# line_sensor.net
KiCad netlist of a schematic drawn in EasyEDA Pro
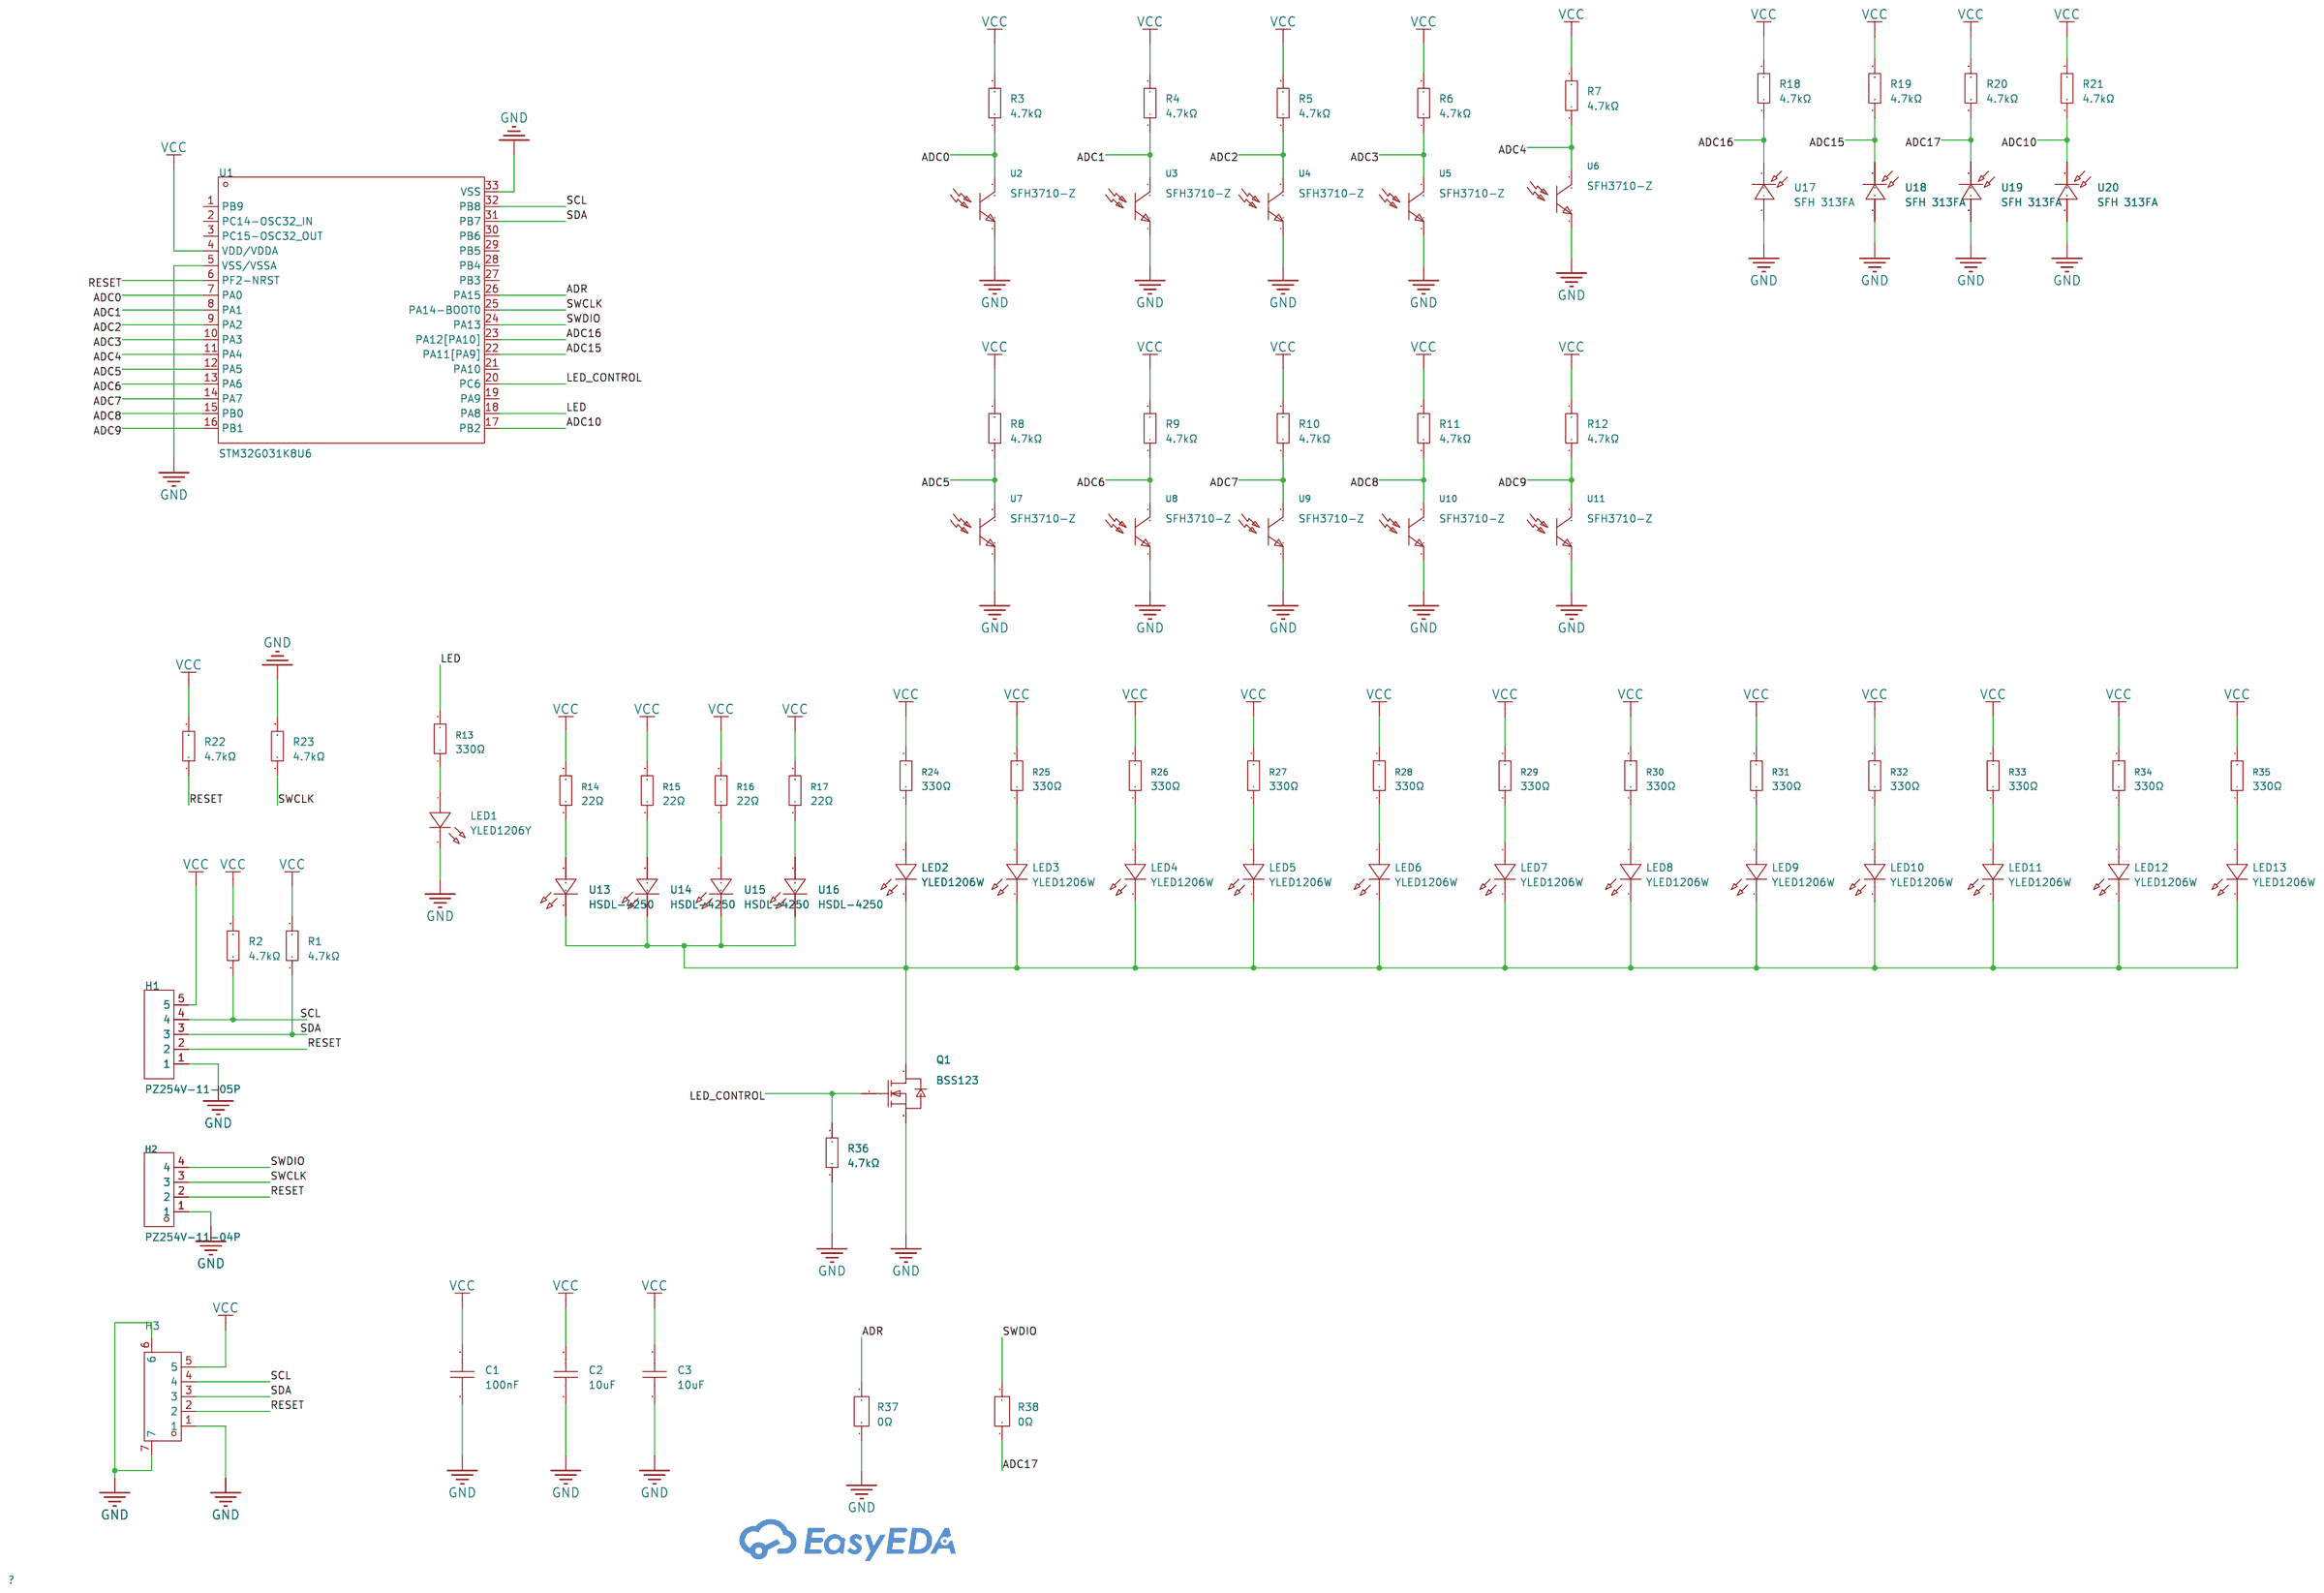
[diagram p0: schematic sheet]

(export (version "E")
  (design (tool "Eeschema 10.0.6"))
  (components
    (comp (ref "C1")
      (value "100nF")
      (footprint "easyedapro:C0805")
      (description "Capacitance:100nF Tolerance:±10% Tolerance:±10% Voltage Rating:50V Temperature Coefficient:X7R")
      (fields
        (field (name "Manufacturer Part") "CC0805KRX7R9BB104")
        (field (name "Manufacturer") "YAGEO(国巨)")
      )
      (libsource (lib "easyedapro") (part "CC0805KRX7R9BB104"))
    )
    (comp (ref "C2")
      (value "10uF")
      (footprint "easyedapro:C0805")
      (description "Capacitance:10uF Tolerance:±10% Tolerance:±10% Voltage Rating:50V Temperature Coefficient:X5R")
      (fields
        (field (name "Manufacturer Part") "CL21A106KBYQNNE")
        (field (name "Manufacturer") "SAMSUNG(三星)")
      )
      (libsource (lib "easyedapro") (part "CL21A106KBYQNNE"))
    )
    (comp (ref "C3")
      (value "10uF")
      (footprint "easyedapro:C0805")
      (description "Capacitance:10uF Tolerance:±10% Tolerance:±10% Voltage Rating:50V Temperature Coefficient:X5R")
      (fields
        (field (name "Manufacturer Part") "CL21A106KBYQNNE")
        (field (name "Manufacturer") "SAMSUNG(三星)")
      )
      (libsource (lib "easyedapro") (part "CL21A106KBYQNNE"))
    )
    (comp (ref "H1")
      (value "PZ254V-11-05P")
      (footprint "easyedapro:HDR-TH_5P-P2.54-V-M")
      (fields (field (name "Manufacturer") "XFCN(兴飞)"))
      (libsource (lib "easyedapro") (part "PZ254V-11-05P"))
    )
    (comp (ref "H2")
      (value "PZ254V-11-04P")
      (footprint "easyedapro:HDR-TH_4P-P2.54-V-M")
      (fields (field (name "Manufacturer") "XFCN(兴飞)"))
      (libsource (lib "easyedapro") (part "PZ254V-11-04P_C2691448"))
    )
    (comp (ref "H3")
      (value "GT-F0509SR15-05SMT01")
      (footprint "easyedapro:CONN-SMD_GT-F0509SR15-05SMT01")
      (fields (field (name "Manufacturer") "G-Switch(品赞)"))
      (libsource (lib "easyedapro") (part "GT-F0509SR15-05SMT01"))
    )
    (comp (ref "LED1")
      (value "YLED1206Y")
      (footprint "easyedapro:LED1206-FD")
      (fields (field (name "Manufacturer") "YONGYUTAI(永裕泰)"))
      (libsource (lib "easyedapro") (part "YLED1206Y"))
    )
    (comp (ref "LED2")
      (value "YLED1206W")
      (footprint "easyedapro:LED1206-R-RD")
      (fields (field (name "Manufacturer") "YONGYUTAI(永裕泰)"))
      (libsource (lib "easyedapro") (part "YLED1206W"))
    )
    (comp (ref "LED3")
      (value "YLED1206W")
      (footprint "easyedapro:LED1206-R-RD")
      (fields (field (name "Manufacturer") "YONGYUTAI(永裕泰)"))
      (libsource (lib "easyedapro") (part "YLED1206W"))
    )
    (comp (ref "LED4")
      (value "YLED1206W")
      (footprint "easyedapro:LED1206-R-RD")
      (fields (field (name "Manufacturer") "YONGYUTAI(永裕泰)"))
      (libsource (lib "easyedapro") (part "YLED1206W"))
    )
    (comp (ref "LED5")
      (value "YLED1206W")
      (footprint "easyedapro:LED1206-R-RD")
      (fields (field (name "Manufacturer") "YONGYUTAI(永裕泰)"))
      (libsource (lib "easyedapro") (part "YLED1206W"))
    )
    (comp (ref "LED6")
      (value "YLED1206W")
      (footprint "easyedapro:LED1206-R-RD")
      (fields (field (name "Manufacturer") "YONGYUTAI(永裕泰)"))
      (libsource (lib "easyedapro") (part "YLED1206W"))
    )
    (comp (ref "LED7")
      (value "YLED1206W")
      (footprint "easyedapro:LED1206-R-RD")
      (fields (field (name "Manufacturer") "YONGYUTAI(永裕泰)"))
      (libsource (lib "easyedapro") (part "YLED1206W"))
    )
    (comp (ref "LED8")
      (value "YLED1206W")
      (footprint "easyedapro:LED1206-R-RD")
      (fields (field (name "Manufacturer") "YONGYUTAI(永裕泰)"))
      (libsource (lib "easyedapro") (part "YLED1206W"))
    )
    (comp (ref "LED9")
      (value "YLED1206W")
      (footprint "easyedapro:LED1206-R-RD")
      (fields (field (name "Manufacturer") "YONGYUTAI(永裕泰)"))
      (libsource (lib "easyedapro") (part "YLED1206W"))
    )
    (comp (ref "LED10")
      (value "YLED1206W")
      (footprint "easyedapro:LED1206-R-RD")
      (fields (field (name "Manufacturer") "YONGYUTAI(永裕泰)"))
      (libsource (lib "easyedapro") (part "YLED1206W"))
    )
    (comp (ref "LED11")
      (value "YLED1206W")
      (footprint "easyedapro:LED1206-R-RD")
      (fields (field (name "Manufacturer") "YONGYUTAI(永裕泰)"))
      (libsource (lib "easyedapro") (part "YLED1206W"))
    )
    (comp (ref "LED12")
      (value "YLED1206W")
      (footprint "easyedapro:LED1206-R-RD")
      (fields (field (name "Manufacturer") "YONGYUTAI(永裕泰)"))
      (libsource (lib "easyedapro") (part "YLED1206W"))
    )
    (comp (ref "LED13")
      (value "YLED1206W")
      (footprint "easyedapro:LED1206-R-RD")
      (fields (field (name "Manufacturer") "YONGYUTAI(永裕泰)"))
      (libsource (lib "easyedapro") (part "YLED1206W"))
    )
    (comp (ref "Q1")
      (value "BSS123")
      (footprint "easyedapro:SOT-23-3_L3.0-W1.7-P0.95-LS2.9-BR")
      (fields (field (name "Manufacturer") "Siliup(矽普)"))
      (libsource (lib "easyedapro") (part "BSS123_C41355122"))
    )
    (comp (ref "R1")
      (value "4.7kΩ")
      (footprint "easyedapro:R0805")
      (fields
        (field (name "Manufacturer Part") "0805W8F4701T5E")
        (field (name "Manufacturer") "UNI-ROYAL(厚声)")
      )
      (libsource (lib "easyedapro") (part "0805W8F4701T5E"))
    )
    (comp (ref "R2")
      (value "4.7kΩ")
      (footprint "easyedapro:R0805")
      (fields
        (field (name "Manufacturer Part") "0805W8F4701T5E")
        (field (name "Manufacturer") "UNI-ROYAL(厚声)")
      )
      (libsource (lib "easyedapro") (part "0805W8F4701T5E"))
    )
    (comp (ref "R3")
      (value "4.7kΩ")
      (footprint "easyedapro:R0805")
      (fields
        (field (name "Manufacturer Part") "0805W8F4701T5E")
        (field (name "Manufacturer") "UNI-ROYAL(厚声)")
      )
      (libsource (lib "easyedapro") (part "0805W8F4701T5E"))
    )
    (comp (ref "R4")
      (value "4.7kΩ")
      (footprint "easyedapro:R0805")
      (fields
        (field (name "Manufacturer Part") "0805W8F4701T5E")
        (field (name "Manufacturer") "UNI-ROYAL(厚声)")
      )
      (libsource (lib "easyedapro") (part "0805W8F4701T5E"))
    )
    (comp (ref "R5")
      (value "4.7kΩ")
      (footprint "easyedapro:R0805")
      (fields
        (field (name "Manufacturer Part") "0805W8F4701T5E")
        (field (name "Manufacturer") "UNI-ROYAL(厚声)")
      )
      (libsource (lib "easyedapro") (part "0805W8F4701T5E"))
    )
    (comp (ref "R6")
      (value "4.7kΩ")
      (footprint "easyedapro:R0805")
      (fields
        (field (name "Manufacturer Part") "0805W8F4701T5E")
        (field (name "Manufacturer") "UNI-ROYAL(厚声)")
      )
      (libsource (lib "easyedapro") (part "0805W8F4701T5E"))
    )
    (comp (ref "R7")
      (value "4.7kΩ")
      (footprint "easyedapro:R0805")
      (fields
        (field (name "Manufacturer Part") "0805W8F4701T5E")
        (field (name "Manufacturer") "UNI-ROYAL(厚声)")
      )
      (libsource (lib "easyedapro") (part "0805W8F4701T5E"))
    )
    (comp (ref "R8")
      (value "4.7kΩ")
      (footprint "easyedapro:R0805")
      (fields
        (field (name "Manufacturer Part") "0805W8F4701T5E")
        (field (name "Manufacturer") "UNI-ROYAL(厚声)")
      )
      (libsource (lib "easyedapro") (part "0805W8F4701T5E"))
    )
    (comp (ref "R9")
      (value "4.7kΩ")
      (footprint "easyedapro:R0805")
      (fields
        (field (name "Manufacturer Part") "0805W8F4701T5E")
        (field (name "Manufacturer") "UNI-ROYAL(厚声)")
      )
      (libsource (lib "easyedapro") (part "0805W8F4701T5E"))
    )
    (comp (ref "R10")
      (value "4.7kΩ")
      (footprint "easyedapro:R0805")
      (fields
        (field (name "Manufacturer Part") "0805W8F4701T5E")
        (field (name "Manufacturer") "UNI-ROYAL(厚声)")
      )
      (libsource (lib "easyedapro") (part "0805W8F4701T5E"))
    )
    (comp (ref "R11")
      (value "4.7kΩ")
      (footprint "easyedapro:R0805")
      (fields
        (field (name "Manufacturer Part") "0805W8F4701T5E")
        (field (name "Manufacturer") "UNI-ROYAL(厚声)")
      )
      (libsource (lib "easyedapro") (part "0805W8F4701T5E"))
    )
    (comp (ref "R12")
      (value "4.7kΩ")
      (footprint "easyedapro:R0805")
      (fields
        (field (name "Manufacturer Part") "0805W8F4701T5E")
        (field (name "Manufacturer") "UNI-ROYAL(厚声)")
      )
      (libsource (lib "easyedapro") (part "0805W8F4701T5E"))
    )
    (comp (ref "R13")
      (value "330Ω")
      (footprint "easyedapro:R0805")
      (fields
        (field (name "Manufacturer Part") "0805W8F3300T5E")
        (field (name "Manufacturer") "UNI-ROYAL(厚声)")
      )
      (libsource (lib "easyedapro") (part "0805W8F3300T5E"))
    )
    (comp (ref "R14")
      (value "22Ω")
      (footprint "easyedapro:R0805")
      (fields
        (field (name "Manufacturer Part") "0805W8F3300T5E")
        (field (name "Manufacturer") "UNI-ROYAL(厚声)")
      )
      (libsource (lib "easyedapro") (part "0805W8F3300T5E"))
    )
    (comp (ref "R15")
      (value "22Ω")
      (footprint "easyedapro:R0805")
      (fields
        (field (name "Manufacturer Part") "0805W8F3300T5E")
        (field (name "Manufacturer") "UNI-ROYAL(厚声)")
      )
      (libsource (lib "easyedapro") (part "0805W8F3300T5E"))
    )
    (comp (ref "R16")
      (value "22Ω")
      (footprint "easyedapro:R0805")
      (fields
        (field (name "Manufacturer Part") "0805W8F3300T5E")
        (field (name "Manufacturer") "UNI-ROYAL(厚声)")
      )
      (libsource (lib "easyedapro") (part "0805W8F3300T5E"))
    )
    (comp (ref "R17")
      (value "22Ω")
      (footprint "easyedapro:R0805")
      (fields
        (field (name "Manufacturer Part") "0805W8F3300T5E")
        (field (name "Manufacturer") "UNI-ROYAL(厚声)")
      )
      (libsource (lib "easyedapro") (part "0805W8F3300T5E"))
    )
    (comp (ref "R18")
      (value "4.7kΩ")
      (footprint "easyedapro:R0805")
      (fields
        (field (name "Manufacturer Part") "0805W8F4701T5E")
        (field (name "Manufacturer") "UNI-ROYAL(厚声)")
      )
      (libsource (lib "easyedapro") (part "0805W8F4701T5E"))
    )
    (comp (ref "R19")
      (value "4.7kΩ")
      (footprint "easyedapro:R0805")
      (fields
        (field (name "Manufacturer Part") "0805W8F4701T5E")
        (field (name "Manufacturer") "UNI-ROYAL(厚声)")
      )
      (libsource (lib "easyedapro") (part "0805W8F4701T5E"))
    )
    (comp (ref "R20")
      (value "4.7kΩ")
      (footprint "easyedapro:R0805")
      (fields
        (field (name "Manufacturer Part") "0805W8F4701T5E")
        (field (name "Manufacturer") "UNI-ROYAL(厚声)")
      )
      (libsource (lib "easyedapro") (part "0805W8F4701T5E"))
    )
    (comp (ref "R21")
      (value "4.7kΩ")
      (footprint "easyedapro:R0805")
      (fields
        (field (name "Manufacturer Part") "0805W8F4701T5E")
        (field (name "Manufacturer") "UNI-ROYAL(厚声)")
      )
      (libsource (lib "easyedapro") (part "0805W8F4701T5E"))
    )
    (comp (ref "R22")
      (value "4.7kΩ")
      (footprint "easyedapro:R0805")
      (fields
        (field (name "Manufacturer Part") "0805W8F4701T5E")
        (field (name "Manufacturer") "UNI-ROYAL(厚声)")
      )
      (libsource (lib "easyedapro") (part "0805W8F4701T5E"))
    )
    (comp (ref "R23")
      (value "4.7kΩ")
      (footprint "easyedapro:R0805")
      (fields
        (field (name "Manufacturer Part") "0805W8F4701T5E")
        (field (name "Manufacturer") "UNI-ROYAL(厚声)")
      )
      (libsource (lib "easyedapro") (part "0805W8F4701T5E"))
    )
    (comp (ref "R24")
      (value "330Ω")
      (footprint "easyedapro:R0805")
      (fields
        (field (name "Manufacturer Part") "0805W8F3300T5E")
        (field (name "Manufacturer") "UNI-ROYAL(厚声)")
      )
      (libsource (lib "easyedapro") (part "0805W8F3300T5E"))
    )
    (comp (ref "R25")
      (value "330Ω")
      (footprint "easyedapro:R0805")
      (fields
        (field (name "Manufacturer Part") "0805W8F3300T5E")
        (field (name "Manufacturer") "UNI-ROYAL(厚声)")
      )
      (libsource (lib "easyedapro") (part "0805W8F3300T5E"))
    )
    (comp (ref "R26")
      (value "330Ω")
      (footprint "easyedapro:R0805")
      (fields
        (field (name "Manufacturer Part") "0805W8F3300T5E")
        (field (name "Manufacturer") "UNI-ROYAL(厚声)")
      )
      (libsource (lib "easyedapro") (part "0805W8F3300T5E"))
    )
    (comp (ref "R27")
      (value "330Ω")
      (footprint "easyedapro:R0805")
      (fields
        (field (name "Manufacturer Part") "0805W8F3300T5E")
        (field (name "Manufacturer") "UNI-ROYAL(厚声)")
      )
      (libsource (lib "easyedapro") (part "0805W8F3300T5E"))
    )
    (comp (ref "R28")
      (value "330Ω")
      (footprint "easyedapro:R0805")
      (fields
        (field (name "Manufacturer Part") "0805W8F3300T5E")
        (field (name "Manufacturer") "UNI-ROYAL(厚声)")
      )
      (libsource (lib "easyedapro") (part "0805W8F3300T5E"))
    )
    (comp (ref "R29")
      (value "330Ω")
      (footprint "easyedapro:R0805")
      (fields
        (field (name "Manufacturer Part") "0805W8F3300T5E")
        (field (name "Manufacturer") "UNI-ROYAL(厚声)")
      )
      (libsource (lib "easyedapro") (part "0805W8F3300T5E"))
    )
    (comp (ref "R30")
      (value "330Ω")
      (footprint "easyedapro:R0805")
      (fields
        (field (name "Manufacturer Part") "0805W8F3300T5E")
        (field (name "Manufacturer") "UNI-ROYAL(厚声)")
      )
      (libsource (lib "easyedapro") (part "0805W8F3300T5E"))
    )
    (comp (ref "R31")
      (value "330Ω")
      (footprint "easyedapro:R0805")
      (fields
        (field (name "Manufacturer Part") "0805W8F3300T5E")
        (field (name "Manufacturer") "UNI-ROYAL(厚声)")
      )
      (libsource (lib "easyedapro") (part "0805W8F3300T5E"))
    )
    (comp (ref "R32")
      (value "330Ω")
      (footprint "easyedapro:R0805")
      (fields
        (field (name "Manufacturer Part") "0805W8F3300T5E")
        (field (name "Manufacturer") "UNI-ROYAL(厚声)")
      )
      (libsource (lib "easyedapro") (part "0805W8F3300T5E"))
    )
    (comp (ref "R33")
      (value "330Ω")
      (footprint "easyedapro:R0805")
      (fields
        (field (name "Manufacturer Part") "0805W8F3300T5E")
        (field (name "Manufacturer") "UNI-ROYAL(厚声)")
      )
      (libsource (lib "easyedapro") (part "0805W8F3300T5E"))
    )
    (comp (ref "R34")
      (value "330Ω")
      (footprint "easyedapro:R0805")
      (fields
        (field (name "Manufacturer Part") "0805W8F3300T5E")
        (field (name "Manufacturer") "UNI-ROYAL(厚声)")
      )
      (libsource (lib "easyedapro") (part "0805W8F3300T5E"))
    )
    (comp (ref "R35")
      (value "330Ω")
      (footprint "easyedapro:R0805")
      (fields
        (field (name "Manufacturer Part") "0805W8F3300T5E")
        (field (name "Manufacturer") "UNI-ROYAL(厚声)")
      )
      (libsource (lib "easyedapro") (part "0805W8F3300T5E"))
    )
    (comp (ref "R36")
      (value "4.7kΩ")
      (footprint "easyedapro:R0805")
      (fields
        (field (name "Manufacturer Part") "0805W8F4701T5E")
        (field (name "Manufacturer") "UNI-ROYAL(厚声)")
      )
      (libsource (lib "easyedapro") (part "0805W8F4701T5E"))
    )
    (comp (ref "R37")
      (value "0Ω")
      (footprint "easyedapro:R0603")
      (fields (field (name "Manufacturer Part") "FRC0603P000 TS") (field (name "Manufacturer") "FOJAN(富捷)"))
      (libsource (lib "easyedapro") (part "FRC0603P000 TS"))
    )
    (comp (ref "R38")
      (value "0Ω")
      (footprint "easyedapro:R0603")
      (fields (field (name "Manufacturer Part") "FRC0603P000 TS") (field (name "Manufacturer") "FOJAN(富捷)"))
      (libsource (lib "easyedapro") (part "FRC0603P000 TS"))
    )
    (comp (ref "U1")
      (value "STM32G031K8U6")
      (footprint "easyedapro:UFQFPN-32_L5.0-W5.0-P0.50-BL-EP")
      (fields (field (name "Manufacturer") "ST(意法半导体)"))
      (libsource (lib "easyedapro") (part "STM32G031K8U6"))
    )
    (comp (ref "U2")
      (value "SFH3710-Z")
      (footprint "easyedapro:OPTO-SMD_SFH3710-Z")
      (fields (field (name "Manufacturer") "OSRAM(欧司朗)"))
      (libsource (lib "easyedapro") (part "SFH3710-Z"))
    )
    (comp (ref "U3")
      (value "SFH3710-Z")
      (footprint "easyedapro:OPTO-SMD_SFH3710-Z")
      (fields (field (name "Manufacturer") "OSRAM(欧司朗)"))
      (libsource (lib "easyedapro") (part "SFH3710-Z"))
    )
    (comp (ref "U4")
      (value "SFH3710-Z")
      (footprint "easyedapro:OPTO-SMD_SFH3710-Z")
      (fields (field (name "Manufacturer") "OSRAM(欧司朗)"))
      (libsource (lib "easyedapro") (part "SFH3710-Z"))
    )
    (comp (ref "U5")
      (value "SFH3710-Z")
      (footprint "easyedapro:OPTO-SMD_SFH3710-Z")
      (fields (field (name "Manufacturer") "OSRAM(欧司朗)"))
      (libsource (lib "easyedapro") (part "SFH3710-Z"))
    )
    (comp (ref "U6")
      (value "SFH3710-Z")
      (footprint "easyedapro:OPTO-SMD_SFH3710-Z")
      (fields (field (name "Manufacturer") "OSRAM(欧司朗)"))
      (libsource (lib "easyedapro") (part "SFH3710-Z"))
    )
    (comp (ref "U7")
      (value "SFH3710-Z")
      (footprint "easyedapro:OPTO-SMD_SFH3710-Z")
      (fields (field (name "Manufacturer") "OSRAM(欧司朗)"))
      (libsource (lib "easyedapro") (part "SFH3710-Z"))
    )
    (comp (ref "U8")
      (value "SFH3710-Z")
      (footprint "easyedapro:OPTO-SMD_SFH3710-Z")
      (fields (field (name "Manufacturer") "OSRAM(欧司朗)"))
      (libsource (lib "easyedapro") (part "SFH3710-Z"))
    )
    (comp (ref "U9")
      (value "SFH3710-Z")
      (footprint "easyedapro:OPTO-SMD_SFH3710-Z")
      (fields (field (name "Manufacturer") "OSRAM(欧司朗)"))
      (libsource (lib "easyedapro") (part "SFH3710-Z"))
    )
    (comp (ref "U10")
      (value "SFH3710-Z")
      (footprint "easyedapro:OPTO-SMD_SFH3710-Z")
      (fields (field (name "Manufacturer") "OSRAM(欧司朗)"))
      (libsource (lib "easyedapro") (part "SFH3710-Z"))
    )
    (comp (ref "U11")
      (value "SFH3710-Z")
      (footprint "easyedapro:OPTO-SMD_SFH3710-Z")
      (fields (field (name "Manufacturer") "OSRAM(欧司朗)"))
      (libsource (lib "easyedapro") (part "SFH3710-Z"))
    )
    (comp (ref "U13")
      (value "HSDL-4250")
      (footprint "easyedapro:LED-TH_BD5.0-P2.54-FD-1")
      (fields (field (name "Manufacturer") "LITEON(光宝)"))
      (libsource (lib "easyedapro") (part "HSDL-4250"))
    )
    (comp (ref "U14")
      (value "HSDL-4250")
      (footprint "easyedapro:LED-TH_BD5.0-P2.54-FD-1")
      (fields (field (name "Manufacturer") "LITEON(光宝)"))
      (libsource (lib "easyedapro") (part "HSDL-4250"))
    )
    (comp (ref "U15")
      (value "HSDL-4250")
      (footprint "easyedapro:LED-TH_BD5.0-P2.54-FD-1")
      (fields (field (name "Manufacturer") "LITEON(光宝)"))
      (libsource (lib "easyedapro") (part "HSDL-4250"))
    )
    (comp (ref "U16")
      (value "HSDL-4250")
      (footprint "easyedapro:LED-TH_BD5.0-P2.54-FD-1")
      (fields (field (name "Manufacturer") "LITEON(光宝)"))
      (libsource (lib "easyedapro") (part "HSDL-4250"))
    )
    (comp (ref "U17")
      (value "SFH 313FA")
      (footprint "easyedapro:OPTO-TH_BD5.7-P2.54-D0.8")
      (fields (field (name "Manufacturer") "OSRAM(欧司朗)"))
      (libsource (lib "easyedapro") (part "SFH 313FA"))
    )
    (comp (ref "U18")
      (value "SFH 313FA")
      (footprint "easyedapro:OPTO-TH_BD5.7-P2.54-D0.8")
      (fields (field (name "Manufacturer") "OSRAM(欧司朗)"))
      (libsource (lib "easyedapro") (part "SFH 313FA"))
    )
    (comp (ref "U19")
      (value "SFH 313FA")
      (footprint "easyedapro:OPTO-TH_BD5.7-P2.54-D0.8")
      (fields (field (name "Manufacturer") "OSRAM(欧司朗)"))
      (libsource (lib "easyedapro") (part "SFH 313FA"))
    )
    (comp (ref "U20")
      (value "SFH 313FA")
      (footprint "easyedapro:OPTO-TH_BD5.7-P2.54-D0.8")
      (fields (field (name "Manufacturer") "OSRAM(欧司朗)"))
      (libsource (lib "easyedapro") (part "SFH 313FA"))
    )
  )
  (nets
    (net (code "1") (name "/ADC0") (class "Default")
      (node (ref "R3") (pin "1") (pinfunction "1_1") (pintype "input"))
      (node (ref "U1") (pin "7") (pinfunction "PA0_7") (pintype "unspecified"))
      (node (ref "U2") (pin "2") (pinfunction "C_2") (pintype "input"))
    )
    (net (code "2") (name "/ADC1") (class "Default")
      (node (ref "R4") (pin "1") (pinfunction "1_1") (pintype "input"))
      (node (ref "U1") (pin "8") (pinfunction "PA1_8") (pintype "unspecified"))
      (node (ref "U3") (pin "2") (pinfunction "C_2") (pintype "input"))
    )
    (net (code "3") (name "/ADC2") (class "Default")
      (node (ref "R5") (pin "1") (pinfunction "1_1") (pintype "input"))
      (node (ref "U1") (pin "9") (pinfunction "PA2_9") (pintype "unspecified"))
      (node (ref "U4") (pin "2") (pinfunction "C_2") (pintype "input"))
    )
    (net (code "4") (name "/ADC3") (class "Default")
      (node (ref "R6") (pin "1") (pinfunction "1_1") (pintype "input"))
      (node (ref "U1") (pin "10") (pinfunction "PA3_10") (pintype "unspecified"))
      (node (ref "U5") (pin "2") (pinfunction "C_2") (pintype "input"))
    )
    (net (code "5") (name "/ADC4") (class "Default")
      (node (ref "R7") (pin "1") (pinfunction "1_1") (pintype "input"))
      (node (ref "U1") (pin "11") (pinfunction "PA4_11") (pintype "unspecified"))
      (node (ref "U6") (pin "2") (pinfunction "C_2") (pintype "input"))
    )
    (net (code "6") (name "/ADC5") (class "Default")
      (node (ref "R8") (pin "1") (pinfunction "1_1") (pintype "input"))
      (node (ref "U1") (pin "12") (pinfunction "PA5_12") (pintype "unspecified"))
      (node (ref "U7") (pin "2") (pinfunction "C_2") (pintype "input"))
    )
    (net (code "7") (name "/ADC6") (class "Default")
      (node (ref "R9") (pin "1") (pinfunction "1_1") (pintype "input"))
      (node (ref "U1") (pin "13") (pinfunction "PA6_13") (pintype "unspecified"))
      (node (ref "U8") (pin "2") (pinfunction "C_2") (pintype "input"))
    )
    (net (code "8") (name "/ADC7") (class "Default")
      (node (ref "R10") (pin "1") (pinfunction "1_1") (pintype "input"))
      (node (ref "U1") (pin "14") (pinfunction "PA7_14") (pintype "unspecified"))
      (node (ref "U9") (pin "2") (pinfunction "C_2") (pintype "input"))
    )
    (net (code "9") (name "/ADC8") (class "Default")
      (node (ref "R11") (pin "1") (pinfunction "1_1") (pintype "input"))
      (node (ref "U1") (pin "15") (pinfunction "PB0_15") (pintype "unspecified"))
      (node (ref "U10") (pin "2") (pinfunction "C_2") (pintype "input"))
    )
    (net (code "10") (name "/ADC9") (class "Default")
      (node (ref "R12") (pin "1") (pinfunction "1_1") (pintype "input"))
      (node (ref "U1") (pin "16") (pinfunction "PB1_16") (pintype "unspecified"))
      (node (ref "U11") (pin "2") (pinfunction "C_2") (pintype "input"))
    )
    (net (code "11") (name "/ADC10") (class "Default")
      (node (ref "R21") (pin "1") (pinfunction "1_1") (pintype "input"))
      (node (ref "U1") (pin "17") (pinfunction "PB2_17") (pintype "unspecified"))
      (node (ref "U20") (pin "1") (pinfunction "C_1") (pintype "unspecified"))
    )
    (net (code "12") (name "/ADC15") (class "Default")
      (node (ref "R19") (pin "1") (pinfunction "1_1") (pintype "input"))
      (node (ref "U1") (pin "22") (pinfunction "PA11[PA9]_22") (pintype "unspecified"))
      (node (ref "U18") (pin "1") (pinfunction "C_1") (pintype "unspecified"))
    )
    (net (code "13") (name "/ADC16") (class "Default")
      (node (ref "R18") (pin "1") (pinfunction "1_1") (pintype "input"))
      (node (ref "U1") (pin "23") (pinfunction "PA12[PA10]_23") (pintype "unspecified"))
      (node (ref "U17") (pin "1") (pinfunction "C_1") (pintype "unspecified"))
    )
    (net (code "14") (name "/ADC17") (class "Default")
      (node (ref "R20") (pin "1") (pinfunction "1_1") (pintype "input"))
      (node (ref "R38") (pin "1") (pinfunction "1_1") (pintype "unspecified"))
      (node (ref "U19") (pin "1") (pinfunction "C_1") (pintype "unspecified"))
    )
    (net (code "15") (name "/ADR") (class "Default")
      (node (ref "R37") (pin "2") (pinfunction "2_2") (pintype "unspecified"))
      (node (ref "U1") (pin "26") (pinfunction "PA15_26") (pintype "unspecified"))
    )
    (net (code "16") (name "/LED") (class "Default")
      (node (ref "R13") (pin "2") (pinfunction "2_2") (pintype "input"))
      (node (ref "U1") (pin "18") (pinfunction "PA8_18") (pintype "unspecified"))
    )
    (net (code "17") (name "/LED_CONTROL") (class "Default")
      (node (ref "Q1") (pin "1") (pinfunction "G_1") (pintype "unspecified"))
      (node (ref "R36") (pin "2") (pinfunction "2_2") (pintype "input"))
      (node (ref "U1") (pin "20") (pinfunction "PC6_20") (pintype "unspecified"))
    )
    (net (code "18") (name "/RESET") (class "Default")
      (node (ref "H1") (pin "2") (pinfunction "2_2") (pintype "unspecified"))
      (node (ref "H2") (pin "2") (pinfunction "2_2") (pintype "input"))
      (node (ref "H3") (pin "2") (pinfunction "2_2") (pintype "unspecified"))
      (node (ref "R22") (pin "1") (pinfunction "1_1") (pintype "input"))
      (node (ref "U1") (pin "6") (pinfunction "PF2-NRST_6") (pintype "unspecified"))
    )
    (net (code "19") (name "/SCL") (class "Default")
      (node (ref "H1") (pin "4") (pinfunction "4_4") (pintype "unspecified"))
      (node (ref "H3") (pin "4") (pinfunction "4_4") (pintype "unspecified"))
      (node (ref "R2") (pin "1") (pinfunction "1_1") (pintype "input"))
      (node (ref "U1") (pin "32") (pinfunction "PB8_32") (pintype "unspecified"))
    )
    (net (code "20") (name "/SDA") (class "Default")
      (node (ref "H1") (pin "3") (pinfunction "3_3") (pintype "unspecified"))
      (node (ref "H3") (pin "3") (pinfunction "3_3") (pintype "unspecified"))
      (node (ref "R1") (pin "1") (pinfunction "1_1") (pintype "input"))
      (node (ref "U1") (pin "31") (pinfunction "PB7_31") (pintype "unspecified"))
    )
    (net (code "21") (name "/SWCLK") (class "Default")
      (node (ref "H2") (pin "3") (pinfunction "3_3") (pintype "input"))
      (node (ref "R23") (pin "1") (pinfunction "1_1") (pintype "input"))
      (node (ref "U1") (pin "25") (pinfunction "PA14-BOOT0_25") (pintype "unspecified"))
    )
    (net (code "22") (name "/SWDIO") (class "Default")
      (node (ref "H2") (pin "4") (pinfunction "4_4") (pintype "input"))
      (node (ref "R38") (pin "2") (pinfunction "2_2") (pintype "unspecified"))
      (node (ref "U1") (pin "24") (pinfunction "PA13_24") (pintype "unspecified"))
    )
    (net (code "23") (name "GND") (class "Default")
      (node (ref "C1") (pin "1") (pinfunction "1_1") (pintype "unspecified"))
      (node (ref "C2") (pin "1") (pinfunction "1_1") (pintype "unspecified"))
      (node (ref "C3") (pin "1") (pinfunction "1_1") (pintype "unspecified"))
      (node (ref "H1") (pin "1") (pinfunction "1_1") (pintype "unspecified"))
      (node (ref "H2") (pin "1") (pinfunction "1_1") (pintype "input"))
      (node (ref "H3") (pin "1") (pinfunction "1_1") (pintype "unspecified"))
      (node (ref "H3") (pin "6") (pinfunction "6_6") (pintype "unspecified"))
      (node (ref "H3") (pin "7") (pinfunction "7_7") (pintype "unspecified"))
      (node (ref "LED1") (pin "2") (pinfunction "C_2") (pintype "unspecified"))
      (node (ref "Q1") (pin "2") (pinfunction "S_2") (pintype "unspecified"))
      (node (ref "R23") (pin "2") (pinfunction "2_2") (pintype "input"))
      (node (ref "R36") (pin "1") (pinfunction "1_1") (pintype "input"))
      (node (ref "R37") (pin "1") (pinfunction "1_1") (pintype "unspecified"))
      (node (ref "U1") (pin "33") (pinfunction "VSS_33") (pintype "unspecified"))
      (node (ref "U1") (pin "5") (pinfunction "VSS/VSSA_5") (pintype "unspecified"))
      (node (ref "U10") (pin "1") (pinfunction "E_1") (pintype "input"))
      (node (ref "U11") (pin "1") (pinfunction "E_1") (pintype "input"))
      (node (ref "U17") (pin "2") (pinfunction "A_2") (pintype "unspecified"))
      (node (ref "U18") (pin "2") (pinfunction "A_2") (pintype "unspecified"))
      (node (ref "U19") (pin "2") (pinfunction "A_2") (pintype "unspecified"))
      (node (ref "U2") (pin "1") (pinfunction "E_1") (pintype "input"))
      (node (ref "U20") (pin "2") (pinfunction "A_2") (pintype "unspecified"))
      (node (ref "U3") (pin "1") (pinfunction "E_1") (pintype "input"))
      (node (ref "U4") (pin "1") (pinfunction "E_1") (pintype "input"))
      (node (ref "U5") (pin "1") (pinfunction "E_1") (pintype "input"))
      (node (ref "U6") (pin "1") (pinfunction "E_1") (pintype "input"))
      (node (ref "U7") (pin "1") (pinfunction "E_1") (pintype "input"))
      (node (ref "U8") (pin "1") (pinfunction "E_1") (pintype "input"))
      (node (ref "U9") (pin "1") (pinfunction "E_1") (pintype "input"))
    )
    (net (code "24") (name "Net-(LED1-A)") (class "Default")
      (node (ref "LED1") (pin "1") (pinfunction "A_1") (pintype "unspecified"))
      (node (ref "R13") (pin "1") (pinfunction "1_1") (pintype "input"))
    )
    (net (code "25") (name "Net-(LED2-A)") (class "Default")
      (node (ref "LED2") (pin "1") (pinfunction "A_1") (pintype "unspecified"))
      (node (ref "R24") (pin "1") (pinfunction "1_1") (pintype "input"))
    )
    (net (code "26") (name "Net-(LED3-A)") (class "Default")
      (node (ref "LED3") (pin "1") (pinfunction "A_1") (pintype "unspecified"))
      (node (ref "R25") (pin "1") (pinfunction "1_1") (pintype "input"))
    )
    (net (code "27") (name "Net-(LED4-A)") (class "Default")
      (node (ref "LED4") (pin "1") (pinfunction "A_1") (pintype "unspecified"))
      (node (ref "R26") (pin "1") (pinfunction "1_1") (pintype "input"))
    )
    (net (code "28") (name "Net-(LED5-A)") (class "Default")
      (node (ref "LED5") (pin "1") (pinfunction "A_1") (pintype "unspecified"))
      (node (ref "R27") (pin "1") (pinfunction "1_1") (pintype "input"))
    )
    (net (code "29") (name "Net-(LED6-A)") (class "Default")
      (node (ref "LED6") (pin "1") (pinfunction "A_1") (pintype "unspecified"))
      (node (ref "R28") (pin "1") (pinfunction "1_1") (pintype "input"))
    )
    (net (code "30") (name "Net-(LED7-A)") (class "Default")
      (node (ref "LED7") (pin "1") (pinfunction "A_1") (pintype "unspecified"))
      (node (ref "R29") (pin "1") (pinfunction "1_1") (pintype "input"))
    )
    (net (code "31") (name "Net-(LED8-A)") (class "Default")
      (node (ref "LED8") (pin "1") (pinfunction "A_1") (pintype "unspecified"))
      (node (ref "R30") (pin "1") (pinfunction "1_1") (pintype "input"))
    )
    (net (code "32") (name "Net-(LED9-A)") (class "Default")
      (node (ref "LED9") (pin "1") (pinfunction "A_1") (pintype "unspecified"))
      (node (ref "R31") (pin "1") (pinfunction "1_1") (pintype "input"))
    )
    (net (code "33") (name "Net-(LED10-A)") (class "Default")
      (node (ref "LED10") (pin "1") (pinfunction "A_1") (pintype "unspecified"))
      (node (ref "R32") (pin "1") (pinfunction "1_1") (pintype "input"))
    )
    (net (code "34") (name "Net-(LED10-K)") (class "Default")
      (node (ref "LED10") (pin "2") (pinfunction "K_2") (pintype "unspecified"))
      (node (ref "LED11") (pin "2") (pinfunction "K_2") (pintype "unspecified"))
      (node (ref "LED12") (pin "2") (pinfunction "K_2") (pintype "unspecified"))
      (node (ref "LED13") (pin "2") (pinfunction "K_2") (pintype "unspecified"))
      (node (ref "LED2") (pin "2") (pinfunction "K_2") (pintype "unspecified"))
      (node (ref "LED3") (pin "2") (pinfunction "K_2") (pintype "unspecified"))
      (node (ref "LED4") (pin "2") (pinfunction "K_2") (pintype "unspecified"))
      (node (ref "LED5") (pin "2") (pinfunction "K_2") (pintype "unspecified"))
      (node (ref "LED6") (pin "2") (pinfunction "K_2") (pintype "unspecified"))
      (node (ref "LED7") (pin "2") (pinfunction "K_2") (pintype "unspecified"))
      (node (ref "LED8") (pin "2") (pinfunction "K_2") (pintype "unspecified"))
      (node (ref "LED9") (pin "2") (pinfunction "K_2") (pintype "unspecified"))
      (node (ref "Q1") (pin "3") (pinfunction "D_3") (pintype "unspecified"))
      (node (ref "U13") (pin "2") (pinfunction "C_2") (pintype "unspecified"))
      (node (ref "U14") (pin "2") (pinfunction "C_2") (pintype "unspecified"))
      (node (ref "U15") (pin "2") (pinfunction "C_2") (pintype "unspecified"))
      (node (ref "U16") (pin "2") (pinfunction "C_2") (pintype "unspecified"))
    )
    (net (code "35") (name "Net-(LED11-A)") (class "Default")
      (node (ref "LED11") (pin "1") (pinfunction "A_1") (pintype "unspecified"))
      (node (ref "R33") (pin "1") (pinfunction "1_1") (pintype "input"))
    )
    (net (code "36") (name "Net-(LED12-A)") (class "Default")
      (node (ref "LED12") (pin "1") (pinfunction "A_1") (pintype "unspecified"))
      (node (ref "R34") (pin "1") (pinfunction "1_1") (pintype "input"))
    )
    (net (code "37") (name "Net-(LED13-A)") (class "Default")
      (node (ref "LED13") (pin "1") (pinfunction "A_1") (pintype "unspecified"))
      (node (ref "R35") (pin "1") (pinfunction "1_1") (pintype "input"))
    )
    (net (code "38") (name "Net-(U13-A)") (class "Default")
      (node (ref "R14") (pin "1") (pinfunction "1_1") (pintype "input"))
      (node (ref "U13") (pin "1") (pinfunction "A_1") (pintype "unspecified"))
    )
    (net (code "39") (name "Net-(U14-A)") (class "Default")
      (node (ref "R15") (pin "1") (pinfunction "1_1") (pintype "input"))
      (node (ref "U14") (pin "1") (pinfunction "A_1") (pintype "unspecified"))
    )
    (net (code "40") (name "Net-(U15-A)") (class "Default")
      (node (ref "R16") (pin "1") (pinfunction "1_1") (pintype "input"))
      (node (ref "U15") (pin "1") (pinfunction "A_1") (pintype "unspecified"))
    )
    (net (code "41") (name "Net-(U16-A)") (class "Default")
      (node (ref "R17") (pin "1") (pinfunction "1_1") (pintype "input"))
      (node (ref "U16") (pin "1") (pinfunction "A_1") (pintype "unspecified"))
    )
    (net (code "42") (name "VCC") (class "Default")
      (node (ref "C1") (pin "2") (pinfunction "2_2") (pintype "unspecified"))
      (node (ref "C2") (pin "2") (pinfunction "2_2") (pintype "unspecified"))
      (node (ref "C3") (pin "2") (pinfunction "2_2") (pintype "unspecified"))
      (node (ref "H1") (pin "5") (pinfunction "5_5") (pintype "unspecified"))
      (node (ref "H3") (pin "5") (pinfunction "5_5") (pintype "unspecified"))
      (node (ref "R1") (pin "2") (pinfunction "2_2") (pintype "input"))
      (node (ref "R10") (pin "2") (pinfunction "2_2") (pintype "input"))
      (node (ref "R11") (pin "2") (pinfunction "2_2") (pintype "input"))
      (node (ref "R12") (pin "2") (pinfunction "2_2") (pintype "input"))
      (node (ref "R14") (pin "2") (pinfunction "2_2") (pintype "input"))
      (node (ref "R15") (pin "2") (pinfunction "2_2") (pintype "input"))
      (node (ref "R16") (pin "2") (pinfunction "2_2") (pintype "input"))
      (node (ref "R17") (pin "2") (pinfunction "2_2") (pintype "input"))
      (node (ref "R18") (pin "2") (pinfunction "2_2") (pintype "input"))
      (node (ref "R19") (pin "2") (pinfunction "2_2") (pintype "input"))
      (node (ref "R2") (pin "2") (pinfunction "2_2") (pintype "input"))
      (node (ref "R20") (pin "2") (pinfunction "2_2") (pintype "input"))
      (node (ref "R21") (pin "2") (pinfunction "2_2") (pintype "input"))
      (node (ref "R22") (pin "2") (pinfunction "2_2") (pintype "input"))
      (node (ref "R24") (pin "2") (pinfunction "2_2") (pintype "input"))
      (node (ref "R25") (pin "2") (pinfunction "2_2") (pintype "input"))
      (node (ref "R26") (pin "2") (pinfunction "2_2") (pintype "input"))
      (node (ref "R27") (pin "2") (pinfunction "2_2") (pintype "input"))
      (node (ref "R28") (pin "2") (pinfunction "2_2") (pintype "input"))
      (node (ref "R29") (pin "2") (pinfunction "2_2") (pintype "input"))
      (node (ref "R3") (pin "2") (pinfunction "2_2") (pintype "input"))
      (node (ref "R30") (pin "2") (pinfunction "2_2") (pintype "input"))
      (node (ref "R31") (pin "2") (pinfunction "2_2") (pintype "input"))
      (node (ref "R32") (pin "2") (pinfunction "2_2") (pintype "input"))
      (node (ref "R33") (pin "2") (pinfunction "2_2") (pintype "input"))
      (node (ref "R34") (pin "2") (pinfunction "2_2") (pintype "input"))
      (node (ref "R35") (pin "2") (pinfunction "2_2") (pintype "input"))
      (node (ref "R4") (pin "2") (pinfunction "2_2") (pintype "input"))
      (node (ref "R5") (pin "2") (pinfunction "2_2") (pintype "input"))
      (node (ref "R6") (pin "2") (pinfunction "2_2") (pintype "input"))
      (node (ref "R7") (pin "2") (pinfunction "2_2") (pintype "input"))
      (node (ref "R8") (pin "2") (pinfunction "2_2") (pintype "input"))
      (node (ref "R9") (pin "2") (pinfunction "2_2") (pintype "input"))
      (node (ref "U1") (pin "4") (pinfunction "VDD/VDDA_4") (pintype "unspecified"))
    )
    (net (code "43") (name "unconnected-(U1-PA9-Pad19)") (class "Default")
      (node (ref "U1") (pin "19") (pinfunction "PA9_19") (pintype "unspecified"))
    )
    (net (code "44") (name "unconnected-(U1-PA10-Pad21)") (class "Default")
      (node (ref "U1") (pin "21") (pinfunction "PA10_21") (pintype "unspecified"))
    )
    (net (code "45") (name "unconnected-(U1-PB3-Pad27)") (class "Default")
      (node (ref "U1") (pin "27") (pinfunction "PB3_27") (pintype "unspecified"))
    )
    (net (code "46") (name "unconnected-(U1-PB4-Pad28)") (class "Default")
      (node (ref "U1") (pin "28") (pinfunction "PB4_28") (pintype "unspecified"))
    )
    (net (code "47") (name "unconnected-(U1-PB5-Pad29)") (class "Default")
      (node (ref "U1") (pin "29") (pinfunction "PB5_29") (pintype "unspecified"))
    )
    (net (code "48") (name "unconnected-(U1-PB6-Pad30)") (class "Default")
      (node (ref "U1") (pin "30") (pinfunction "PB6_30") (pintype "unspecified"))
    )
    (net (code "49") (name "unconnected-(U1-PB9-Pad1)") (class "Default")
      (node (ref "U1") (pin "1") (pinfunction "PB9_1") (pintype "unspecified"))
    )
    (net (code "50") (name "unconnected-(U1-PC14-OSC32_IN-Pad2)") (class "Default")
      (node (ref "U1") (pin "2") (pinfunction "PC14-OSC32_IN_2") (pintype "unspecified"))
    )
    (net (code "51") (name "unconnected-(U1-PC15-OSC32_OUT-Pad3)") (class "Default")
      (node (ref "U1") (pin "3") (pinfunction "PC15-OSC32_OUT_3") (pintype "unspecified"))
    )
  )
)
